# Motor_Control.net
KiCad netlist of a schematic drawn in Altium Designer
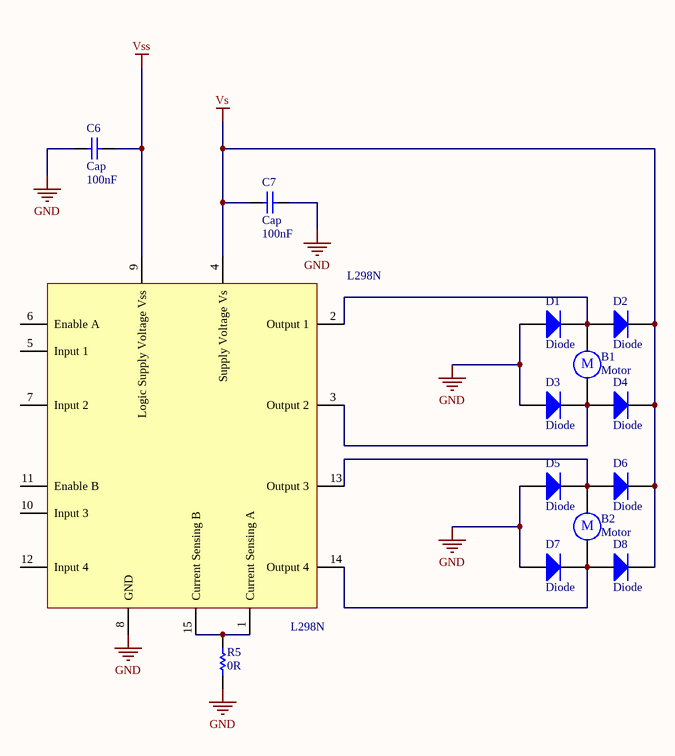
[diagram p0: Motor_Control.SchDoc]

(export (version "E")
  (design (tool "Eeschema 10.0.6"))
  (components
    (comp (ref "B1")
      (value "Motor")
      (footprint "RB5-10.5")
      (description "Motor, General Kind")
      (fields (field (name "PUBLISHER") "Altium Limited"))
      (libsource (lib "Miscellaneous Devices") (part "Motor"))
    )
    (comp (ref "B2")
      (value "Motor")
      (footprint "RB5-10.5")
      (description "Motor, General Kind")
      (fields (field (name "PUBLISHER") "Altium Limited"))
      (libsource (lib "Miscellaneous Devices") (part "Motor"))
    )
    (comp (ref "C6")
      (value "Cap")
      (footprint "RAD-0.3")
      (description "Capacitor")
      (fields (field (name "ALTIUM_VALUE") "100nF") (field (name "PUBLISHER") "Altium Limited"))
      (libsource (lib "Miscellaneous Devices") (part "Cap"))
    )
    (comp (ref "C7")
      (value "Cap")
      (footprint "RAD-0.3")
      (description "Capacitor")
      (fields (field (name "ALTIUM_VALUE") "100nF") (field (name "PUBLISHER") "Altium Limited"))
      (libsource (lib "Miscellaneous Devices") (part "Cap"))
    )
    (comp (ref "D1")
      (value "Diode")
      (footprint "SMC")
      (description "Default Diode")
      (fields (field (name "PUBLISHER") "Altium Limited"))
      (libsource (lib "Miscellaneous Devices") (part "Diode"))
    )
    (comp (ref "D2")
      (value "Diode")
      (footprint "SMC")
      (description "Default Diode")
      (fields (field (name "PUBLISHER") "Altium Limited"))
      (libsource (lib "Miscellaneous Devices") (part "Diode"))
    )
    (comp (ref "D3")
      (value "Diode")
      (footprint "SMC")
      (description "Default Diode")
      (fields (field (name "PUBLISHER") "Altium Limited"))
      (libsource (lib "Miscellaneous Devices") (part "Diode"))
    )
    (comp (ref "D4")
      (value "Diode")
      (footprint "SMC")
      (description "Default Diode")
      (fields (field (name "PUBLISHER") "Altium Limited"))
      (libsource (lib "Miscellaneous Devices") (part "Diode"))
    )
    (comp (ref "D5")
      (value "Diode")
      (footprint "SMC")
      (description "Default Diode")
      (fields (field (name "PUBLISHER") "Altium Limited"))
      (libsource (lib "Miscellaneous Devices") (part "Diode"))
    )
    (comp (ref "D6")
      (value "Diode")
      (footprint "SMC")
      (description "Default Diode")
      (fields (field (name "PUBLISHER") "Altium Limited"))
      (libsource (lib "Miscellaneous Devices") (part "Diode"))
    )
    (comp (ref "D7")
      (value "Diode")
      (footprint "SMC")
      (description "Default Diode")
      (fields (field (name "PUBLISHER") "Altium Limited"))
      (libsource (lib "Miscellaneous Devices") (part "Diode"))
    )
    (comp (ref "D8")
      (value "Diode")
      (footprint "SMC")
      (description "Default Diode")
      (fields (field (name "PUBLISHER") "Altium Limited"))
      (libsource (lib "Miscellaneous Devices") (part "Diode"))
    )
    (comp (ref "L298N") (value "L298N") (footprint "L298N") (libsource (lib "SCHLIB_Autobot") (part "L298N")))
    (comp (ref "R5")
      (value "0R")
      (footprint "AXIAL-0.3")
      (description "Resistor")
      (fields (field (name "PUBLISHER") "Altium Limited"))
      (libsource (lib "Miscellaneous Devices") (part "Res1"))
    )
  )
  (nets
    (net (code "1") (name "GND") (class "Default")
      (node (ref "C6") (pin "2") (pinfunction "2_2") (pintype "passive"))
      (node (ref "C7") (pin "2") (pinfunction "2_2") (pintype "passive"))
      (node (ref "D1") (pin "1") (pinfunction "A_1") (pintype "passive"))
      (node (ref "D3") (pin "1") (pinfunction "A_1") (pintype "passive"))
      (node (ref "D5") (pin "1") (pinfunction "A_1") (pintype "passive"))
      (node (ref "D7") (pin "1") (pinfunction "A_1") (pintype "passive"))
      (node (ref "L298N") (pin "8") (pinfunction "GND_8") (pintype "passive"))
      (node (ref "R5") (pin "1") (pinfunction "1_1") (pintype "passive"))
    )
    (net (code "2") (name "Net-(D1-K)") (class "Default")
      (node (ref "B1") (pin "1") (pinfunction "1_1") (pintype "passive"))
      (node (ref "D1") (pin "2") (pinfunction "K_2") (pintype "passive"))
      (node (ref "D2") (pin "1") (pinfunction "A_1") (pintype "passive"))
      (node (ref "L298N") (pin "2") (pinfunction "Output_1_2") (pintype "passive"))
    )
    (net (code "3") (name "Net-(D3-K)") (class "Default")
      (node (ref "B1") (pin "2") (pinfunction "2_2") (pintype "passive"))
      (node (ref "D3") (pin "2") (pinfunction "K_2") (pintype "passive"))
      (node (ref "D4") (pin "1") (pinfunction "A_1") (pintype "passive"))
      (node (ref "L298N") (pin "3") (pinfunction "Output_2_3") (pintype "passive"))
    )
    (net (code "4") (name "Net-(D5-K)") (class "Default")
      (node (ref "B2") (pin "1") (pinfunction "1_1") (pintype "passive"))
      (node (ref "D5") (pin "2") (pinfunction "K_2") (pintype "passive"))
      (node (ref "D6") (pin "1") (pinfunction "A_1") (pintype "passive"))
      (node (ref "L298N") (pin "13") (pinfunction "Output_3_13") (pintype "passive"))
    )
    (net (code "5") (name "Net-(D7-K)") (class "Default")
      (node (ref "B2") (pin "2") (pinfunction "2_2") (pintype "passive"))
      (node (ref "D7") (pin "2") (pinfunction "K_2") (pintype "passive"))
      (node (ref "D8") (pin "1") (pinfunction "A_1") (pintype "passive"))
      (node (ref "L298N") (pin "14") (pinfunction "Output_4_14") (pintype "passive"))
    )
    (net (code "6") (name "Net-(L298N-Current_Sensing_A)") (class "Default")
      (node (ref "L298N") (pin "1") (pinfunction "Current_Sensing_A_1") (pintype "passive"))
      (node (ref "L298N") (pin "15") (pinfunction "Current_Sensing_B_15") (pintype "passive"))
      (node (ref "R5") (pin "2") (pinfunction "2_2") (pintype "passive"))
    )
    (net (code "7") (name "Vs") (class "Default")
      (node (ref "C7") (pin "1") (pinfunction "1_1") (pintype "passive"))
      (node (ref "D2") (pin "2") (pinfunction "K_2") (pintype "passive"))
      (node (ref "D4") (pin "2") (pinfunction "K_2") (pintype "passive"))
      (node (ref "D6") (pin "2") (pinfunction "K_2") (pintype "passive"))
      (node (ref "D8") (pin "2") (pinfunction "K_2") (pintype "passive"))
      (node (ref "L298N") (pin "4") (pinfunction "Supply_Voltage_Vs_4") (pintype "passive"))
    )
    (net (code "8") (name "Vss") (class "Default")
      (node (ref "C6") (pin "1") (pinfunction "1_1") (pintype "passive"))
      (node (ref "L298N") (pin "9") (pinfunction "Logic_Supply_Voltage_Vss_9") (pintype "passive"))
    )
    (net (code "9") (name "unconnected-(L298N-Enable_A-Pad6)") (class "Default")
      (node (ref "L298N") (pin "6") (pinfunction "Enable_A_6") (pintype "passive"))
    )
    (net (code "10") (name "unconnected-(L298N-Enable_B-Pad11)") (class "Default")
      (node (ref "L298N") (pin "11") (pinfunction "Enable_B_11") (pintype "passive"))
    )
    (net (code "11") (name "unconnected-(L298N-Input_1-Pad5)") (class "Default")
      (node (ref "L298N") (pin "5") (pinfunction "Input_1_5") (pintype "passive"))
    )
    (net (code "12") (name "unconnected-(L298N-Input_2-Pad7)") (class "Default")
      (node (ref "L298N") (pin "7") (pinfunction "Input_2_7") (pintype "passive"))
    )
    (net (code "13") (name "unconnected-(L298N-Input_3-Pad10)") (class "Default")
      (node (ref "L298N") (pin "10") (pinfunction "Input_3_10") (pintype "passive"))
    )
    (net (code "14") (name "unconnected-(L298N-Input_4-Pad12)") (class "Default")
      (node (ref "L298N") (pin "12") (pinfunction "Input_4_12") (pintype "passive"))
    )
  )
)
